# A4a_NodeMCU.net
KiCad netlist of a schematic drawn in EAGLE
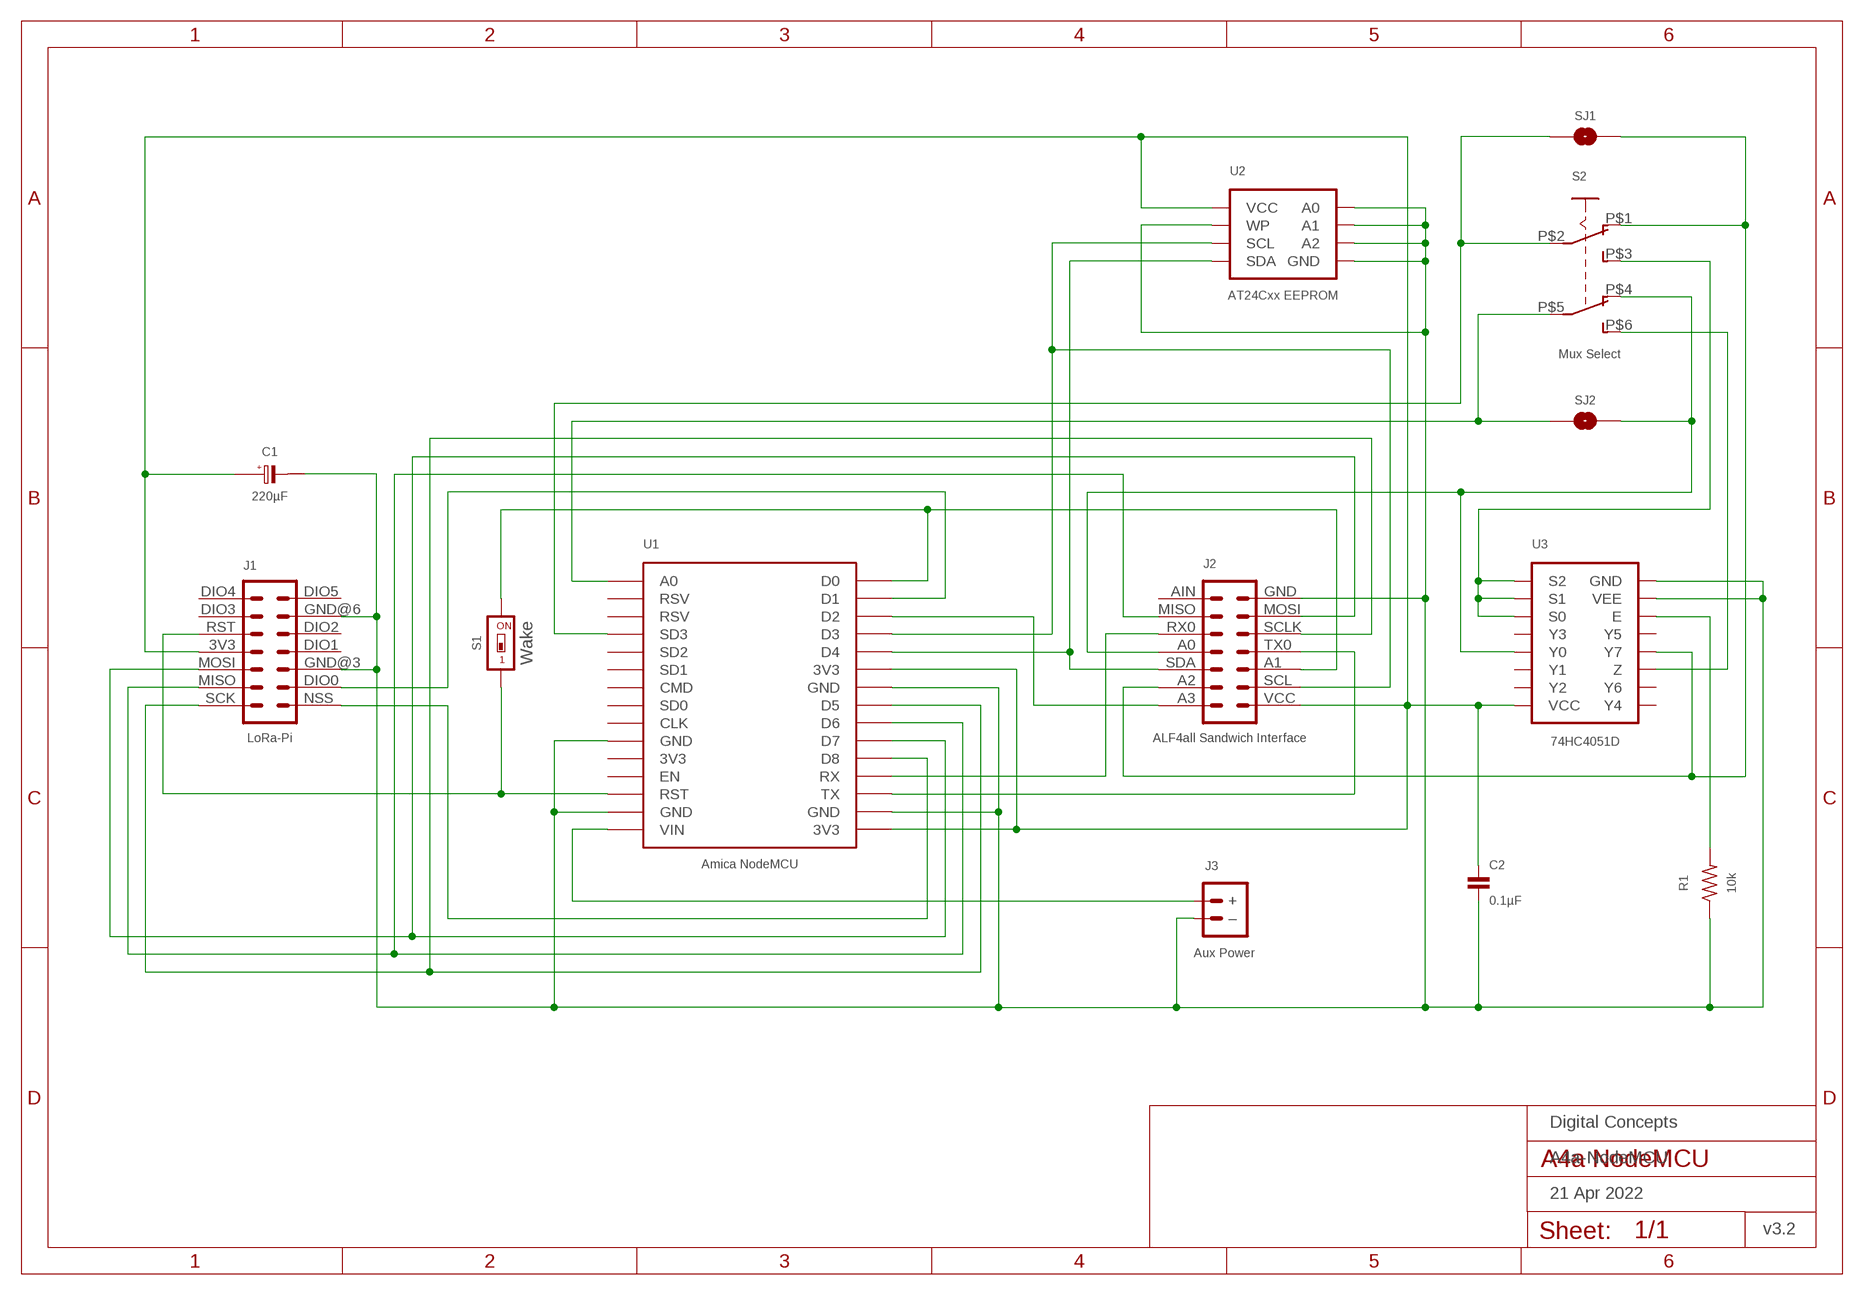
[diagram p0: schematic, sheet 1]

(export (version "E")
  (design (tool "Eeschema 10.0.6"))
  (components
    (comp (ref "C1")
      (value "220µF")
      (footprint "eagle-import:C3528-21")
      (libsource (lib "eagle-import") (part "CAPACITOR-TANTALUM-3528"))
    )
    (comp (ref "C2")
      (value "0.1µF")
      (footprint "eagle-import:C0805")
      (libsource (lib "eagle-import") (part "CAPACITOR-0805"))
    )
    (comp (ref "J1")
      (value "LoRa-Pi")
      (footprint "eagle-import:RFM95W-PI")
      (libsource (lib "eagle-import") (part "RFM95W-PI-HEADER"))
    )
    (comp (ref "J2")
      (value "ALF4all Sandwich Interface")
      (footprint "eagle-import:CONN_2X7-ALF4ALL-PROCESSOR-B")
      (libsource (lib "eagle-import") (part "HEADER-2X7-ALF4ALL-PROCESSOR-B"))
    )
    (comp (ref "J3")
      (value "Aux Power")
      (footprint "eagle-import:JST-PH2.0-2-HORIZONTAL")
      (libsource (lib "eagle-import") (part "JST-PH2.0-2-MALE-HORIZONTALJST-PTH-2"))
    )
    (comp (ref "R1")
      (value "10k")
      (footprint "eagle-import:R0805")
      (libsource (lib "eagle-import") (part "RESISTORR0805"))
    )
    (comp (ref "S1")
      (value "Wake")
      (footprint "eagle-import:SMD-001")
      (libsource (lib "eagle-import") (part "SWITCH-DIP-SWS001"))
    )
    (comp (ref "S2")
      (value "Mux Select")
      (footprint "eagle-import:SWITCH-DPDT-SMD")
      (libsource (lib "eagle-import") (part "SWITCH-DPDT"))
    )
    (comp (ref "SJ1") (value "SJ") (footprint "eagle-import:SJ") (libsource (lib "eagle-import") (part "SJ")))
    (comp (ref "SJ2") (value "SJ") (footprint "eagle-import:SJ") (libsource (lib "eagle-import") (part "SJ")))
    (comp (ref "U1")
      (value "Amica NodeMCU")
      (footprint "eagle-import:AMICA-NODEMCU")
      (libsource (lib "eagle-import") (part "AMICA-NODEMCU"))
    )
    (comp (ref "U2")
      (value "AT24Cxx EEPROM")
      (footprint "eagle-import:SOP-8")
      (libsource (lib "eagle-import") (part "AT24CXX-EEPROM"))
    )
    (comp (ref "U3")
      (value "74HC4051D")
      (footprint "eagle-import:SOP16")
      (libsource (lib "eagle-import") (part "74HC4051D"))
    )
  )
  (nets
    (net (code "1") (name "Net-(C1-+)") (class "Default")
      (node (ref "C1") (pin "1") (pinfunction "+_1") (pintype "passive"))
      (node (ref "C2") (pin "1") (pinfunction "1_1") (pintype "passive"))
      (node (ref "J1") (pin "3V3") (pinfunction "11_3V3") (pintype "passive"))
      (node (ref "J2") (pin "VCC") (pinfunction "1_VCC") (pintype "passive"))
      (node (ref "U1") (pin "3V3@1") (pinfunction "3V3_3V3@1") (pintype "bidirectional"))
      (node (ref "U1") (pin "3V3@10") (pinfunction "3V3_3V3@10") (pintype "bidirectional"))
      (node (ref "U2") (pin "P$8") (pinfunction "VCC_P$8") (pintype "bidirectional"))
      (node (ref "U3") (pin "16") (pinfunction "VCC_16") (pintype "bidirectional"))
    )
    (net (code "2") (name "Net-(C1--)") (class "Default")
      (node (ref "C1") (pin "2") (pinfunction "-_2") (pintype "passive"))
      (node (ref "C2") (pin "2") (pinfunction "2_2") (pintype "passive"))
      (node (ref "J1") (pin "GND@3") (pinfunction "3_GND@3") (pintype "passive"))
      (node (ref "J1") (pin "GND@6") (pinfunction "6_GND@6") (pintype "passive"))
      (node (ref "J2") (pin "GND") (pinfunction "7_GND") (pintype "passive"))
      (node (ref "J3") (pin "-") (pinfunction "–_-") (pintype "power_in"))
      (node (ref "R1") (pin "1") (pinfunction "1_1") (pintype "passive"))
      (node (ref "U1") (pin "GND@2") (pinfunction "GND_GND@2") (pintype "bidirectional"))
      (node (ref "U1") (pin "GND@25") (pinfunction "GND_GND@25") (pintype "bidirectional"))
      (node (ref "U1") (pin "GND@29") (pinfunction "GND_GND@29") (pintype "bidirectional"))
      (node (ref "U1") (pin "GND@9") (pinfunction "GND_GND@9") (pintype "bidirectional"))
      (node (ref "U2") (pin "P$1") (pinfunction "A0_P$1") (pintype "bidirectional"))
      (node (ref "U2") (pin "P$2") (pinfunction "A1_P$2") (pintype "bidirectional"))
      (node (ref "U2") (pin "P$3") (pinfunction "A2_P$3") (pintype "bidirectional"))
      (node (ref "U2") (pin "P$4") (pinfunction "GND_P$4") (pintype "bidirectional"))
      (node (ref "U2") (pin "P$7") (pinfunction "WP_P$7") (pintype "bidirectional"))
      (node (ref "U3") (pin "7") (pinfunction "VEE_7") (pintype "bidirectional"))
      (node (ref "U3") (pin "8") (pinfunction "GND_8") (pintype "bidirectional"))
    )
    (net (code "3") (name "Net-(J1-1)") (class "Default")
      (node (ref "J1") (pin "NSS") (pinfunction "1_NSS") (pintype "passive"))
      (node (ref "U1") (pin "D8") (pinfunction "D8_D8") (pintype "bidirectional"))
    )
    (net (code "4") (name "Net-(J1-2)") (class "Default")
      (node (ref "J1") (pin "DIO0") (pinfunction "2_DIO0") (pintype "passive"))
      (node (ref "U1") (pin "D1") (pinfunction "D1_D1") (pintype "bidirectional"))
    )
    (net (code "5") (name "Net-(J1-10)") (class "Default")
      (node (ref "J1") (pin "RST") (pinfunction "10_RST") (pintype "passive"))
      (node (ref "S1") (pin "1") (pinfunction "1_1") (pintype "passive"))
      (node (ref "U1") (pin "RST") (pinfunction "RST_RST") (pintype "bidirectional"))
    )
    (net (code "6") (name "Net-(J1-12)") (class "Default")
      (node (ref "J1") (pin "MOSI") (pinfunction "12_MOSI") (pintype "passive"))
      (node (ref "J2") (pin "MOSI") (pinfunction "6_MOSI") (pintype "passive"))
      (node (ref "U1") (pin "D7") (pinfunction "D7_D7") (pintype "bidirectional"))
    )
    (net (code "7") (name "Net-(J1-13)") (class "Default")
      (node (ref "J1") (pin "MISO") (pinfunction "13_MISO") (pintype "passive"))
      (node (ref "J2") (pin "MISO") (pinfunction "9_MISO") (pintype "passive"))
      (node (ref "U1") (pin "D6") (pinfunction "D6_D6") (pintype "bidirectional"))
    )
    (net (code "8") (name "Net-(J1-14)") (class "Default")
      (node (ref "J1") (pin "SCK") (pinfunction "14_SCK") (pintype "passive"))
      (node (ref "J2") (pin "SCLK") (pinfunction "5_SCLK") (pintype "passive"))
      (node (ref "U1") (pin "D5") (pinfunction "D5_D5") (pintype "bidirectional"))
    )
    (net (code "9") (name "Net-(J2-2)") (class "Default")
      (node (ref "J2") (pin "SCL") (pinfunction "2_SCL") (pintype "passive"))
      (node (ref "U1") (pin "D3") (pinfunction "D3_D3") (pintype "bidirectional"))
      (node (ref "U2") (pin "P$6") (pinfunction "SCL_P$6") (pintype "bidirectional"))
    )
    (net (code "10") (name "Net-(J2-3)") (class "Default")
      (node (ref "J2") (pin "A1") (pinfunction "3_A1") (pintype "passive"))
      (node (ref "S1") (pin "2") (pinfunction "2_2") (pintype "passive"))
      (node (ref "U1") (pin "D0") (pinfunction "D0_D0") (pintype "bidirectional"))
    )
    (net (code "11") (name "Net-(J2-4)") (class "Default")
      (node (ref "J2") (pin "TX0") (pinfunction "4_TX0") (pintype "passive"))
      (node (ref "U1") (pin "TX") (pinfunction "TX_TX") (pintype "bidirectional"))
    )
    (net (code "12") (name "Net-(J2-10)") (class "Default")
      (node (ref "J2") (pin "RX0") (pinfunction "10_RX0") (pintype "passive"))
      (node (ref "U1") (pin "RX") (pinfunction "RX_RX") (pintype "bidirectional"))
    )
    (net (code "13") (name "Net-(J2-11)") (class "Default")
      (node (ref "J2") (pin "A0") (pinfunction "11_A0") (pintype "passive"))
      (node (ref "S2") (pin "P$4") (pinfunction "O2_P$4") (pintype "passive"))
      (node (ref "SJ2") (pin "2") (pinfunction "2_2") (pintype "passive"))
      (node (ref "U3") (pin "13") (pinfunction "Y0_13") (pintype "bidirectional"))
    )
    (net (code "14") (name "Net-(J2-12)") (class "Default")
      (node (ref "J2") (pin "SDA") (pinfunction "12_SDA") (pintype "passive"))
      (node (ref "U1") (pin "D4") (pinfunction "D4_D4") (pintype "bidirectional"))
      (node (ref "U2") (pin "P$5") (pinfunction "SDA_P$5") (pintype "bidirectional"))
    )
    (net (code "15") (name "Net-(J2-13)") (class "Default")
      (node (ref "J2") (pin "A2") (pinfunction "13_A2") (pintype "passive"))
      (node (ref "S2") (pin "P$1") (pinfunction "O1_P$1") (pintype "passive"))
      (node (ref "SJ1") (pin "2") (pinfunction "2_2") (pintype "passive"))
      (node (ref "U3") (pin "4") (pinfunction "Y7_4") (pintype "bidirectional"))
    )
    (net (code "16") (name "Net-(J2-14)") (class "Default")
      (node (ref "J2") (pin "A3") (pinfunction "14_A3") (pintype "passive"))
      (node (ref "U1") (pin "D2") (pinfunction "D2_D2") (pintype "bidirectional"))
    )
    (net (code "17") (name "Net-(J3-Pad+)") (class "Default")
      (node (ref "J3") (pin "+") (pinfunction "+_+") (pintype "power_in"))
      (node (ref "U1") (pin "VIN") (pinfunction "VIN_VIN") (pintype "bidirectional"))
    )
    (net (code "18") (name "Net-(S2-P1)") (class "Default")
      (node (ref "S2") (pin "P$2") (pinfunction "P1_P$2") (pintype "passive"))
      (node (ref "SJ1") (pin "1") (pinfunction "1_1") (pintype "passive"))
      (node (ref "U1") (pin "SD3") (pinfunction "SD3_SD3") (pintype "bidirectional"))
    )
    (net (code "19") (name "Net-(S2-P2)") (class "Default")
      (node (ref "S2") (pin "P$5") (pinfunction "P2_P$5") (pintype "passive"))
      (node (ref "SJ2") (pin "1") (pinfunction "1_1") (pintype "passive"))
      (node (ref "U1") (pin "A0") (pinfunction "A0_A0") (pintype "bidirectional"))
    )
    (net (code "20") (name "Net-(S2-S1)") (class "Default")
      (node (ref "S2") (pin "P$3") (pinfunction "S1_P$3") (pintype "passive"))
      (node (ref "U3") (pin "10") (pinfunction "S1_10") (pintype "bidirectional"))
      (node (ref "U3") (pin "11") (pinfunction "S0_11") (pintype "bidirectional"))
      (node (ref "U3") (pin "9") (pinfunction "S2_9") (pintype "bidirectional"))
    )
    (net (code "21") (name "Net-(S2-S2)") (class "Default")
      (node (ref "S2") (pin "P$6") (pinfunction "S2_P$6") (pintype "passive"))
      (node (ref "U3") (pin "3") (pinfunction "Z_3") (pintype "bidirectional"))
    )
    (net (code "22") (name "Net-(U3-E)") (class "Default")
      (node (ref "R1") (pin "2") (pinfunction "2_2") (pintype "passive"))
      (node (ref "U3") (pin "6") (pinfunction "E_6") (pintype "bidirectional"))
    )
    (net (code "23") (name "unconnected-(J1-4-PadDIO1)") (class "Default")
      (node (ref "J1") (pin "DIO1") (pinfunction "4_DIO1") (pintype "passive"))
    )
    (net (code "24") (name "unconnected-(J1-5-PadDIO2)") (class "Default")
      (node (ref "J1") (pin "DIO2") (pinfunction "5_DIO2") (pintype "passive"))
    )
    (net (code "25") (name "unconnected-(J1-7-PadDIO5)") (class "Default")
      (node (ref "J1") (pin "DIO5") (pinfunction "7_DIO5") (pintype "passive"))
    )
    (net (code "26") (name "unconnected-(J1-8-PadDIO4)") (class "Default")
      (node (ref "J1") (pin "DIO4") (pinfunction "8_DIO4") (pintype "passive"))
    )
    (net (code "27") (name "unconnected-(J1-9-PadDIO3)") (class "Default")
      (node (ref "J1") (pin "DIO3") (pinfunction "9_DIO3") (pintype "passive"))
    )
    (net (code "28") (name "unconnected-(J2-8-PadAIN)") (class "Default")
      (node (ref "J2") (pin "AIN") (pinfunction "8_AIN") (pintype "passive"))
    )
    (net (code "29") (name "unconnected-(U1-3V3-Pad3V3@26)") (class "Default")
      (node (ref "U1") (pin "3V3@26") (pinfunction "3V3_3V3@26") (pintype "bidirectional"))
    )
    (net (code "30") (name "unconnected-(U1-PadCLK)") (class "Default")
      (node (ref "U1") (pin "CLK") (pinfunction "CLK_CLK") (pintype "bidirectional"))
    )
    (net (code "31") (name "unconnected-(U1-PadCMD)") (class "Default")
      (node (ref "U1") (pin "CMD") (pinfunction "CMD_CMD") (pintype "bidirectional"))
    )
    (net (code "32") (name "unconnected-(U1-PadEN)") (class "Default")
      (node (ref "U1") (pin "EN") (pinfunction "EN_EN") (pintype "bidirectional"))
    )
    (net (code "33") (name "unconnected-(U1-PadSD0)") (class "Default")
      (node (ref "U1") (pin "SD0") (pinfunction "SD0_SD0") (pintype "bidirectional"))
    )
    (net (code "34") (name "unconnected-(U1-PadSD1)") (class "Default")
      (node (ref "U1") (pin "SD1") (pinfunction "SD1_SD1") (pintype "bidirectional"))
    )
    (net (code "35") (name "unconnected-(U1-PadSD2)") (class "Default")
      (node (ref "U1") (pin "SD2") (pinfunction "SD2_SD2") (pintype "bidirectional"))
    )
    (net (code "36") (name "unconnected-(U1-RSV-PadRSV@17)") (class "Default")
      (node (ref "U1") (pin "RSV@17") (pinfunction "RSV_RSV@17") (pintype "bidirectional"))
    )
    (net (code "37") (name "unconnected-(U1-RSV-PadRSV@18)") (class "Default")
      (node (ref "U1") (pin "RSV@18") (pinfunction "RSV_RSV@18") (pintype "bidirectional"))
    )
    (net (code "38") (name "unconnected-(U3-Y1-Pad14)") (class "Default")
      (node (ref "U3") (pin "14") (pinfunction "Y1_14") (pintype "bidirectional"))
    )
    (net (code "39") (name "unconnected-(U3-Y2-Pad15)") (class "Default")
      (node (ref "U3") (pin "15") (pinfunction "Y2_15") (pintype "bidirectional"))
    )
    (net (code "40") (name "unconnected-(U3-Y3-Pad12)") (class "Default")
      (node (ref "U3") (pin "12") (pinfunction "Y3_12") (pintype "bidirectional"))
    )
    (net (code "41") (name "unconnected-(U3-Y4-Pad1)") (class "Default")
      (node (ref "U3") (pin "1") (pinfunction "Y4_1") (pintype "bidirectional"))
    )
    (net (code "42") (name "unconnected-(U3-Y5-Pad5)") (class "Default")
      (node (ref "U3") (pin "5") (pinfunction "Y5_5") (pintype "bidirectional"))
    )
    (net (code "43") (name "unconnected-(U3-Y6-Pad2)") (class "Default")
      (node (ref "U3") (pin "2") (pinfunction "Y6_2") (pintype "bidirectional"))
    )
  )
)
